# pcb.net
KiCad netlist of a schematic drawn in Altium Designer
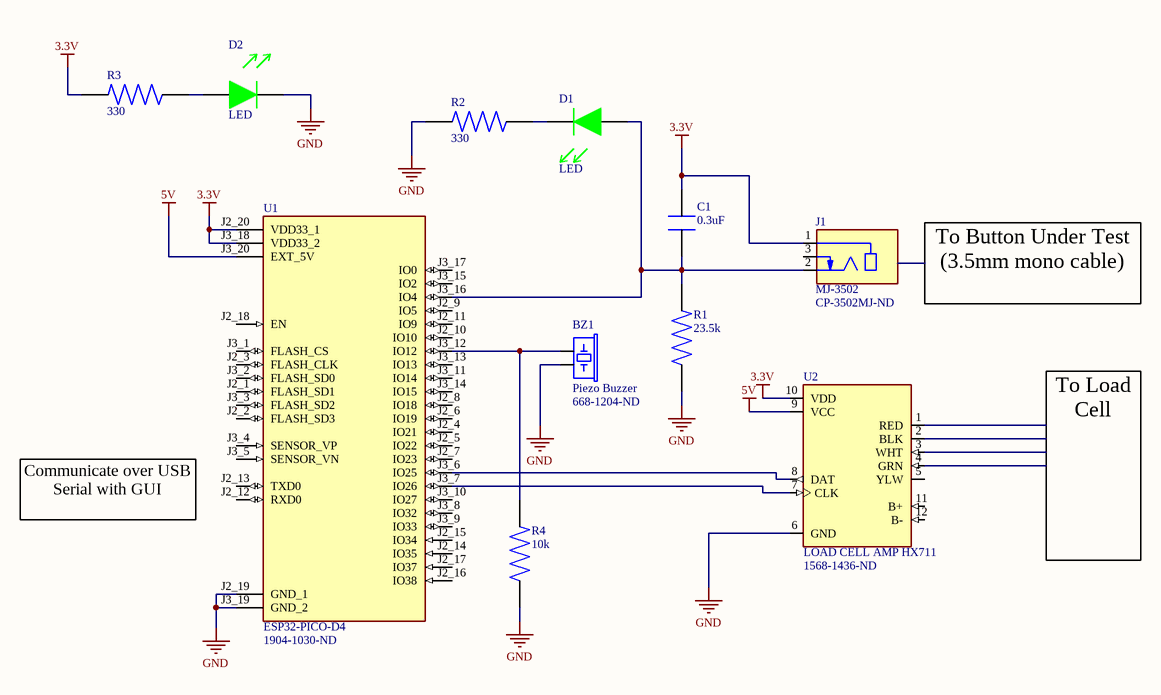
[diagram p0: pcb.SchDoc]

(export (version "E")
  (design (tool "Eeschema 10.0.6"))
  (components
    (comp (ref "BZ1")
      (value "Piezo Buzzer")
      (footprint "AI-3035-TWT-3V-R")
      (description "Audio Indicator Piezo 2VDC 5VDC 9mA 3VDC 100dBAdBA 3000Hz to 4000Hz Through Hole Pin")
      (fields
        (field (name "MANUFACTURER") "Projects Unlimited")
        (field (name "MANUFACTURER PART NUMBER") "AI-3035-TWT-3V-R")
        (field (name "SUPPLIER PART NUMBER 1") "668-1204-ND")
      )
      (libsource (lib "SchematicLibrary") (part "BUZZER"))
    )
    (comp (ref "C1")
      (value "0.3uF")
      (footprint "NET_TIE-12")
      (libsource (lib "SchematicLibrary") (part "CAP"))
    )
    (comp (ref "D1") (value "LED") (footprint "NET_TIE-12") (libsource (lib "SchematicLibrary") (part "LED")))
    (comp (ref "D2") (value "LED") (footprint "NET_TIE-12") (libsource (lib "SchematicLibrary") (part "LED")))
    (comp (ref "J1")
      (value "MJ-3502")
      (footprint "NET_TIE-12")
      (description "3.5 mm, Mono, Right Angle, Through Hole, Threaded Bushing, Audio Jack Connector")
      (fields (field (name "MANUFACTURER") "CUI") (field (name "SUPPLIER PART NUMBER 1") "CP-3502MJ-ND"))
      (libsource (lib "SchematicLibrary") (part "MJ-3502"))
    )
    (comp (ref "R1")
      (value "23.5k")
      (footprint "NET_TIE-12")
      (libsource (lib "SchematicLibrary") (part "RES"))
    )
    (comp (ref "R2") (value "330") (footprint "NET_TIE-12") (libsource (lib "SchematicLibrary") (part "RES")))
    (comp (ref "R3") (value "330") (footprint "NET_TIE-12") (libsource (lib "SchematicLibrary") (part "RES")))
    (comp (ref "R4") (value "10k") (footprint "NET_TIE-12") (libsource (lib "SchematicLibrary") (part "RES")))
    (comp (ref "U1")
      (value "ESP32-PICO-D4")
      (description "ESP32 Wifi Bluetooth Eval Board")
      (fields
        (field (name "MANUFACTURER") "Espressif Systems")
        (field (name "MANUFACTURER PART NUMBER") "ESP32-PICO-KIT")
        (field (name "SUPPLIER PART NUMBER 1") "1904-1030-ND")
      )
      (libsource (lib "SchematicLibrary") (part "ESP32-PICO-KIT"))
    )
    (comp (ref "U2")
      (value "LOAD CELL AMP HX711")
      (description "HX711 Load Cell Amplifier")
      (fields
        (field (name "MANUFACTURER") "SparkFun")
        (field (name "MANUFACTURER PART NUMBER") "SEN-13879")
        (field (name "SUPPLIER PART NUMBER 1") "1568-1436-ND")
      )
      (libsource (lib "SchematicLibrary") (part "LOAD CELL AMP HX711"))
    )
  )
  (nets
    (net (code "1") (name "3.3V") (class "Default")
      (node (ref "C1") (pin "0") (pinfunction "0_0") (pintype "passive"))
      (node (ref "J1") (pin "1") (pinfunction "1_1") (pintype "passive"))
      (node (ref "R3") (pin "2") (pinfunction "2_2") (pintype "passive"))
      (node (ref "U1") (pin "J2_20") (pinfunction "VDD33_1_J2_20") (pintype "power_in"))
      (node (ref "U1") (pin "J3_18") (pinfunction "VDD33_2_J3_18") (pintype "power_in"))
      (node (ref "U2") (pin "10") (pinfunction "VDD_10") (pintype "power_in"))
    )
    (net (code "2") (name "5V") (class "Default")
      (node (ref "U1") (pin "J3_20") (pinfunction "EXT_5V_J3_20") (pintype "power_in"))
      (node (ref "U2") (pin "9") (pinfunction "VCC_9") (pintype "power_in"))
    )
    (net (code "3") (name "GND") (class "Default")
      (node (ref "BZ1") (pin "P$3") (pinfunction "2_P$3") (pintype "passive"))
      (node (ref "D2") (pin "1") (pinfunction "1_1") (pintype "passive"))
      (node (ref "R1") (pin "1") (pinfunction "1_1") (pintype "passive"))
      (node (ref "R2") (pin "2") (pinfunction "2_2") (pintype "passive"))
      (node (ref "R4") (pin "1") (pinfunction "1_1") (pintype "passive"))
      (node (ref "U1") (pin "J2_19") (pinfunction "GND_1_J2_19") (pintype "power_in"))
      (node (ref "U1") (pin "J3_19") (pinfunction "GND_2_J3_19") (pintype "power_in"))
      (node (ref "U2") (pin "6") (pinfunction "GND_6") (pintype "power_in"))
    )
    (net (code "4") (name "Net-(BZ1-1)") (class "Default")
      (node (ref "BZ1") (pin "P$2") (pinfunction "1_P$2") (pintype "passive"))
      (node (ref "R4") (pin "2") (pinfunction "2_2") (pintype "passive"))
      (node (ref "U1") (pin "J3_12") (pinfunction "IO12_J3_12") (pintype "bidirectional"))
    )
    (net (code "5") (name "Net-(D1-Pad1)") (class "Default")
      (node (ref "D1") (pin "1") (pinfunction "1_1") (pintype "passive"))
      (node (ref "R2") (pin "1") (pinfunction "1_1") (pintype "passive"))
    )
    (net (code "6") (name "Net-(D2-Pad0)") (class "Default")
      (node (ref "D2") (pin "0") (pinfunction "0_0") (pintype "passive"))
      (node (ref "R3") (pin "1") (pinfunction "1_1") (pintype "passive"))
    )
    (net (code "7") (name "Net-(U1-IO4)") (class "Default")
      (node (ref "C1") (pin "1") (pinfunction "1_1") (pintype "passive"))
      (node (ref "D1") (pin "0") (pinfunction "0_0") (pintype "passive"))
      (node (ref "J1") (pin "2") (pinfunction "2_2") (pintype "passive"))
      (node (ref "R1") (pin "2") (pinfunction "2_2") (pintype "passive"))
      (node (ref "U1") (pin "J3_16") (pinfunction "IO4_J3_16") (pintype "bidirectional"))
    )
    (net (code "8") (name "Net-(U1-IO25)") (class "Default")
      (node (ref "U1") (pin "J3_6") (pinfunction "IO25_J3_6") (pintype "bidirectional"))
      (node (ref "U2") (pin "8") (pinfunction "DAT_8") (pintype "output"))
    )
    (net (code "9") (name "Net-(U1-IO26)") (class "Default")
      (node (ref "U1") (pin "J3_7") (pinfunction "IO26_J3_7") (pintype "bidirectional"))
      (node (ref "U2") (pin "7") (pinfunction "CLK_7") (pintype "input"))
    )
    (net (code "10") (name "unconnected-(J1-Pad3)") (class "Default")
      (node (ref "J1") (pin "3") (pinfunction "3_3") (pintype "passive"))
    )
    (net (code "11") (name "unconnected-(U1-EN-PadJ2_18)") (class "Default")
      (node (ref "U1") (pin "J2_18") (pinfunction "EN_J2_18") (pintype "input"))
    )
    (net (code "12") (name "unconnected-(U1-FLASH_CLK-PadJ2_3)") (class "Default")
      (node (ref "U1") (pin "J2_3") (pinfunction "FLASH_CLK_J2_3") (pintype "bidirectional"))
    )
    (net (code "13") (name "unconnected-(U1-FLASH_CS-PadJ3_1)") (class "Default")
      (node (ref "U1") (pin "J3_1") (pinfunction "FLASH_CS_J3_1") (pintype "bidirectional"))
    )
    (net (code "14") (name "unconnected-(U1-FLASH_SD0-PadJ3_2)") (class "Default")
      (node (ref "U1") (pin "J3_2") (pinfunction "FLASH_SD0_J3_2") (pintype "bidirectional"))
    )
    (net (code "15") (name "unconnected-(U1-FLASH_SD1-PadJ2_1)") (class "Default")
      (node (ref "U1") (pin "J2_1") (pinfunction "FLASH_SD1_J2_1") (pintype "bidirectional"))
    )
    (net (code "16") (name "unconnected-(U1-FLASH_SD2-PadJ3_3)") (class "Default")
      (node (ref "U1") (pin "J3_3") (pinfunction "FLASH_SD2_J3_3") (pintype "bidirectional"))
    )
    (net (code "17") (name "unconnected-(U1-FLASH_SD3-PadJ2_2)") (class "Default")
      (node (ref "U1") (pin "J2_2") (pinfunction "FLASH_SD3_J2_2") (pintype "bidirectional"))
    )
    (net (code "18") (name "unconnected-(U1-IO0-PadJ3_17)") (class "Default")
      (node (ref "U1") (pin "J3_17") (pinfunction "IO0_J3_17") (pintype "bidirectional"))
    )
    (net (code "19") (name "unconnected-(U1-IO2-PadJ3_15)") (class "Default")
      (node (ref "U1") (pin "J3_15") (pinfunction "IO2_J3_15") (pintype "bidirectional"))
    )
    (net (code "20") (name "unconnected-(U1-IO5-PadJ2_9)") (class "Default")
      (node (ref "U1") (pin "J2_9") (pinfunction "IO5_J2_9") (pintype "bidirectional"))
    )
    (net (code "21") (name "unconnected-(U1-IO9-PadJ2_11)") (class "Default")
      (node (ref "U1") (pin "J2_11") (pinfunction "IO9_J2_11") (pintype "bidirectional"))
    )
    (net (code "22") (name "unconnected-(U1-IO10-PadJ2_10)") (class "Default")
      (node (ref "U1") (pin "J2_10") (pinfunction "IO10_J2_10") (pintype "bidirectional"))
    )
    (net (code "23") (name "unconnected-(U1-IO13-PadJ3_13)") (class "Default")
      (node (ref "U1") (pin "J3_13") (pinfunction "IO13_J3_13") (pintype "bidirectional"))
    )
    (net (code "24") (name "unconnected-(U1-IO14-PadJ3_11)") (class "Default")
      (node (ref "U1") (pin "J3_11") (pinfunction "IO14_J3_11") (pintype "bidirectional"))
    )
    (net (code "25") (name "unconnected-(U1-IO15-PadJ3_14)") (class "Default")
      (node (ref "U1") (pin "J3_14") (pinfunction "IO15_J3_14") (pintype "bidirectional"))
    )
    (net (code "26") (name "unconnected-(U1-IO18-PadJ2_8)") (class "Default")
      (node (ref "U1") (pin "J2_8") (pinfunction "IO18_J2_8") (pintype "bidirectional"))
    )
    (net (code "27") (name "unconnected-(U1-IO19-PadJ2_6)") (class "Default")
      (node (ref "U1") (pin "J2_6") (pinfunction "IO19_J2_6") (pintype "bidirectional"))
    )
    (net (code "28") (name "unconnected-(U1-IO21-PadJ2_4)") (class "Default")
      (node (ref "U1") (pin "J2_4") (pinfunction "IO21_J2_4") (pintype "bidirectional"))
    )
    (net (code "29") (name "unconnected-(U1-IO22-PadJ2_5)") (class "Default")
      (node (ref "U1") (pin "J2_5") (pinfunction "IO22_J2_5") (pintype "bidirectional"))
    )
    (net (code "30") (name "unconnected-(U1-IO23-PadJ2_7)") (class "Default")
      (node (ref "U1") (pin "J2_7") (pinfunction "IO23_J2_7") (pintype "bidirectional"))
    )
    (net (code "31") (name "unconnected-(U1-IO27-PadJ3_10)") (class "Default")
      (node (ref "U1") (pin "J3_10") (pinfunction "IO27_J3_10") (pintype "bidirectional"))
    )
    (net (code "32") (name "unconnected-(U1-IO32-PadJ3_8)") (class "Default")
      (node (ref "U1") (pin "J3_8") (pinfunction "IO32_J3_8") (pintype "bidirectional"))
    )
    (net (code "33") (name "unconnected-(U1-IO33-PadJ3_9)") (class "Default")
      (node (ref "U1") (pin "J3_9") (pinfunction "IO33_J3_9") (pintype "bidirectional"))
    )
    (net (code "34") (name "unconnected-(U1-IO34-PadJ2_15)") (class "Default")
      (node (ref "U1") (pin "J2_15") (pinfunction "IO34_J2_15") (pintype "input"))
    )
    (net (code "35") (name "unconnected-(U1-IO35-PadJ2_14)") (class "Default")
      (node (ref "U1") (pin "J2_14") (pinfunction "IO35_J2_14") (pintype "input"))
    )
    (net (code "36") (name "unconnected-(U1-IO37-PadJ2_17)") (class "Default")
      (node (ref "U1") (pin "J2_17") (pinfunction "IO37_J2_17") (pintype "input"))
    )
    (net (code "37") (name "unconnected-(U1-IO38-PadJ2_16)") (class "Default")
      (node (ref "U1") (pin "J2_16") (pinfunction "IO38_J2_16") (pintype "input"))
    )
    (net (code "38") (name "unconnected-(U1-RXD0-PadJ2_12)") (class "Default")
      (node (ref "U1") (pin "J2_12") (pinfunction "RXD0_J2_12") (pintype "bidirectional"))
    )
    (net (code "39") (name "unconnected-(U1-SENSOR_VN-PadJ3_5)") (class "Default")
      (node (ref "U1") (pin "J3_5") (pinfunction "SENSOR_VN_J3_5") (pintype "input"))
    )
    (net (code "40") (name "unconnected-(U1-SENSOR_VP-PadJ3_4)") (class "Default")
      (node (ref "U1") (pin "J3_4") (pinfunction "SENSOR_VP_J3_4") (pintype "input"))
    )
    (net (code "41") (name "unconnected-(U1-TXD0-PadJ2_13)") (class "Default")
      (node (ref "U1") (pin "J2_13") (pinfunction "TXD0_J2_13") (pintype "bidirectional"))
    )
    (net (code "42") (name "unconnected-(U2-B+-Pad11)") (class "Default")
      (node (ref "U2") (pin "11") (pinfunction "B+_11") (pintype "input"))
    )
    (net (code "43") (name "unconnected-(U2-B--Pad12)") (class "Default")
      (node (ref "U2") (pin "12") (pinfunction "B-_12") (pintype "input"))
    )
    (net (code "44") (name "unconnected-(U2-BLK-Pad2)") (class "Default")
      (node (ref "U2") (pin "2") (pinfunction "BLK_2") (pintype "bidirectional"))
    )
    (net (code "45") (name "unconnected-(U2-GRN-Pad4)") (class "Default")
      (node (ref "U2") (pin "4") (pinfunction "GRN_4") (pintype "input"))
    )
    (net (code "46") (name "unconnected-(U2-RED-Pad1)") (class "Default")
      (node (ref "U2") (pin "1") (pinfunction "RED_1") (pintype "bidirectional"))
    )
    (net (code "47") (name "unconnected-(U2-WHT-Pad3)") (class "Default")
      (node (ref "U2") (pin "3") (pinfunction "WHT_3") (pintype "input"))
    )
    (net (code "48") (name "unconnected-(U2-YLW-Pad5)") (class "Default")
      (node (ref "U2") (pin "5") (pinfunction "YLW_5") (pintype "bidirectional"))
    )
  )
)
